# IPMC_MACP_3.net
KiCad netlist of a schematic drawn in Altium Designer
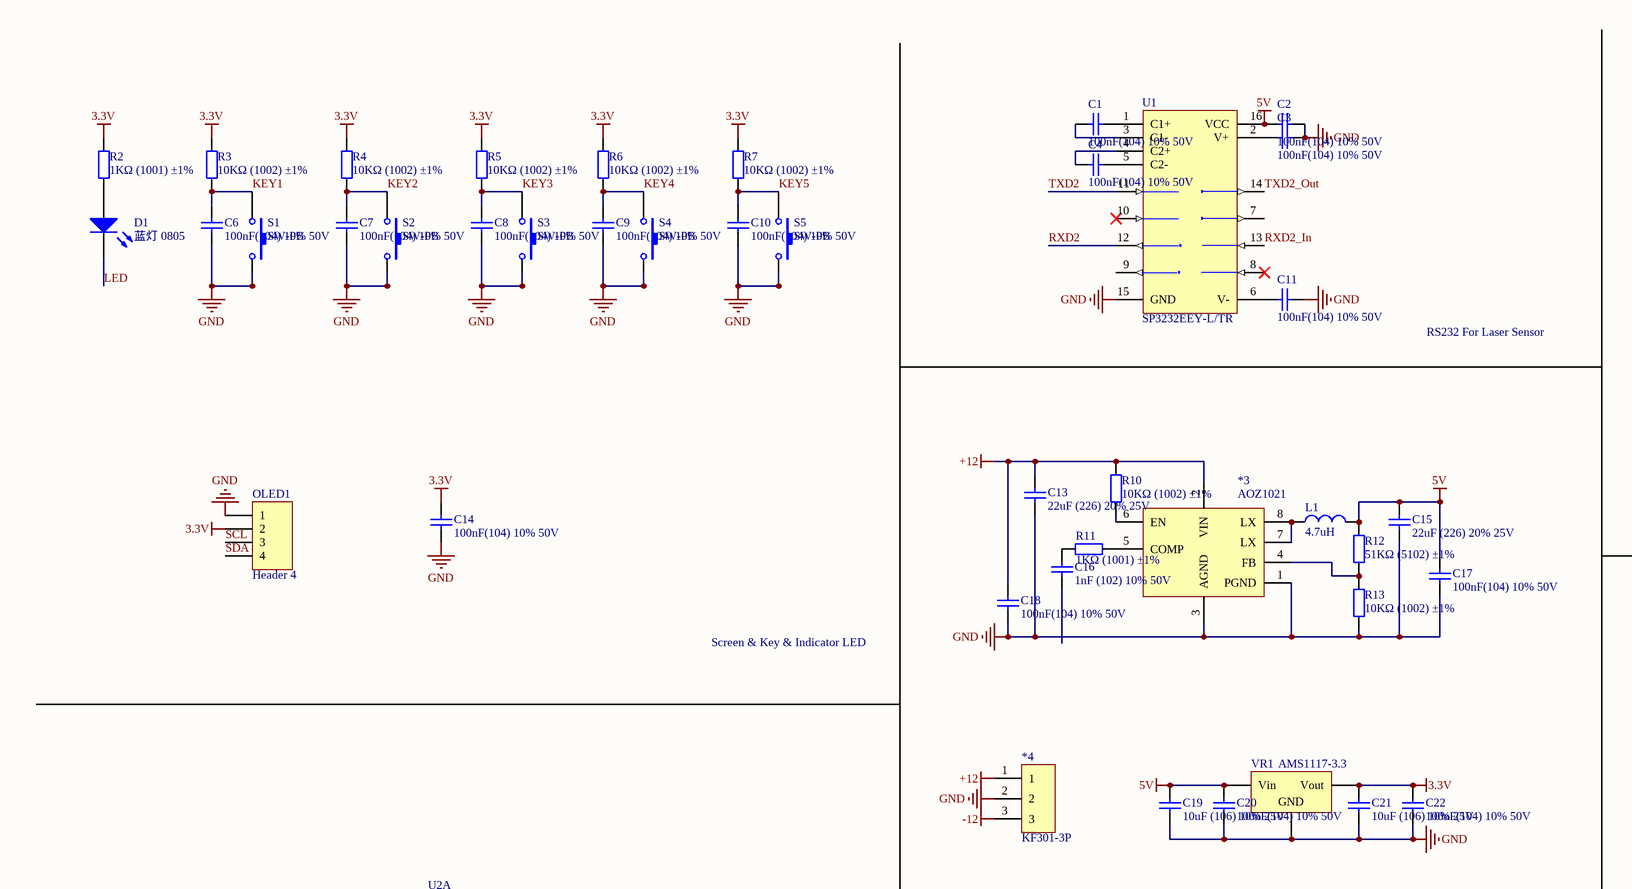
[diagram p0: IPMC_MACP 3.SchDoc, top left]
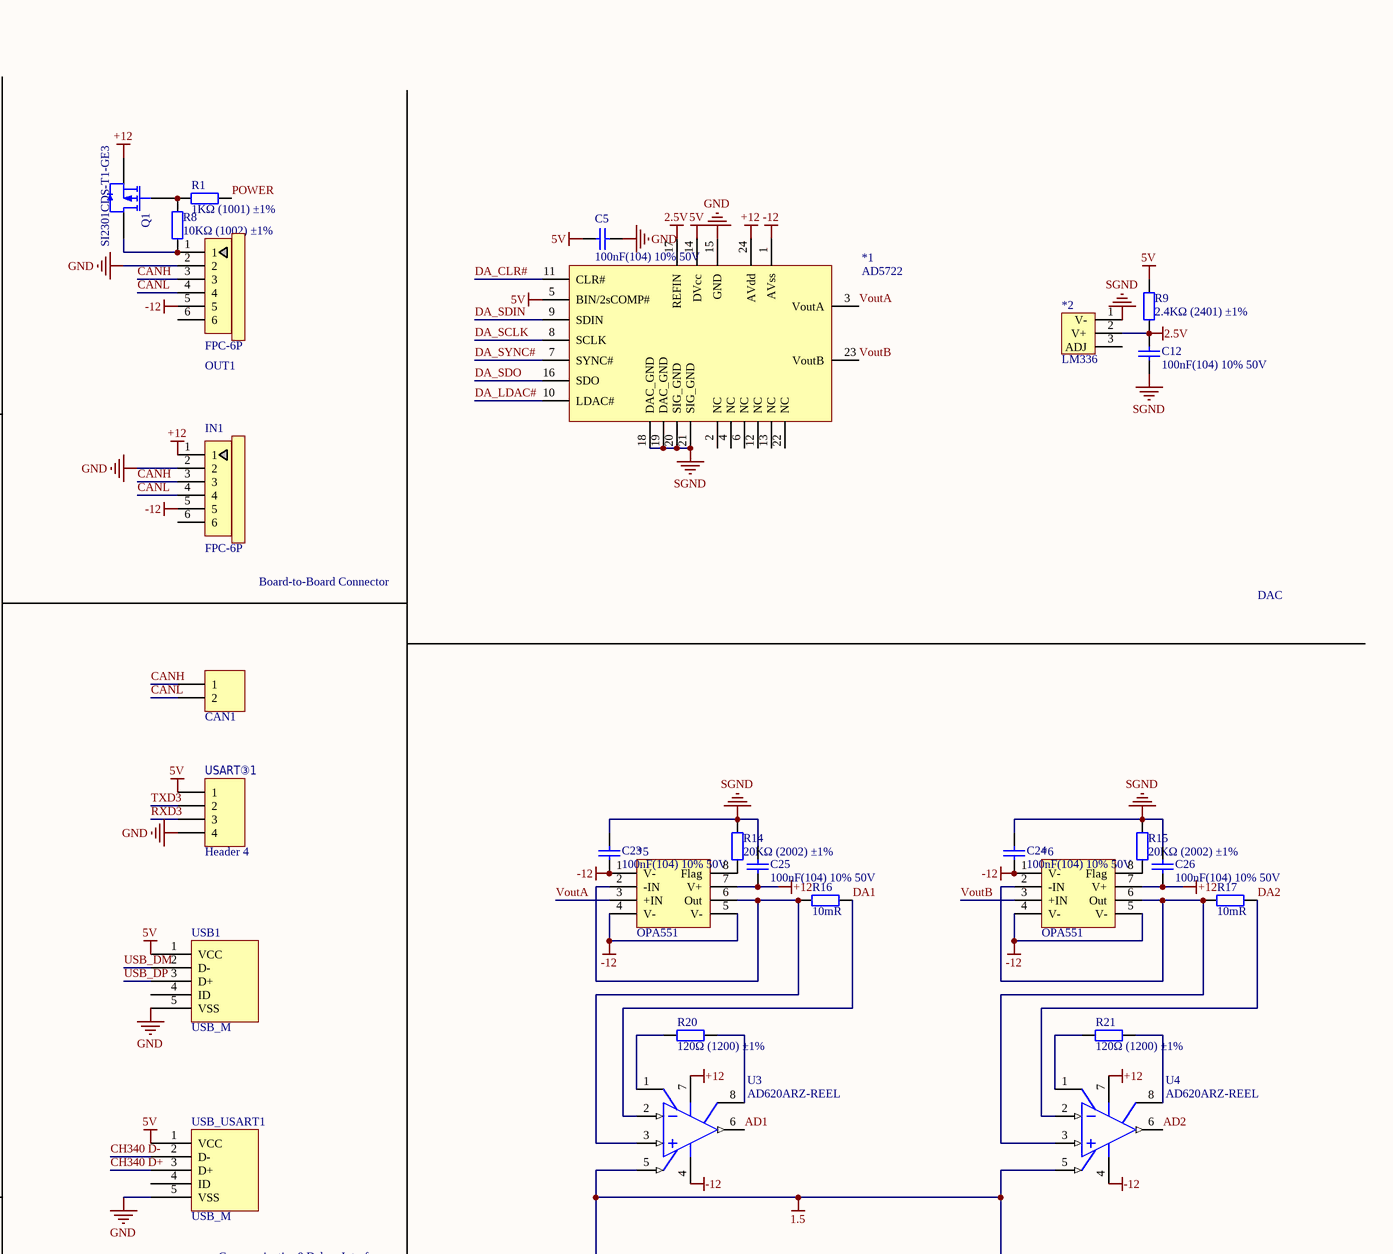
[diagram p1: IPMC_MACP 3.SchDoc, top right]
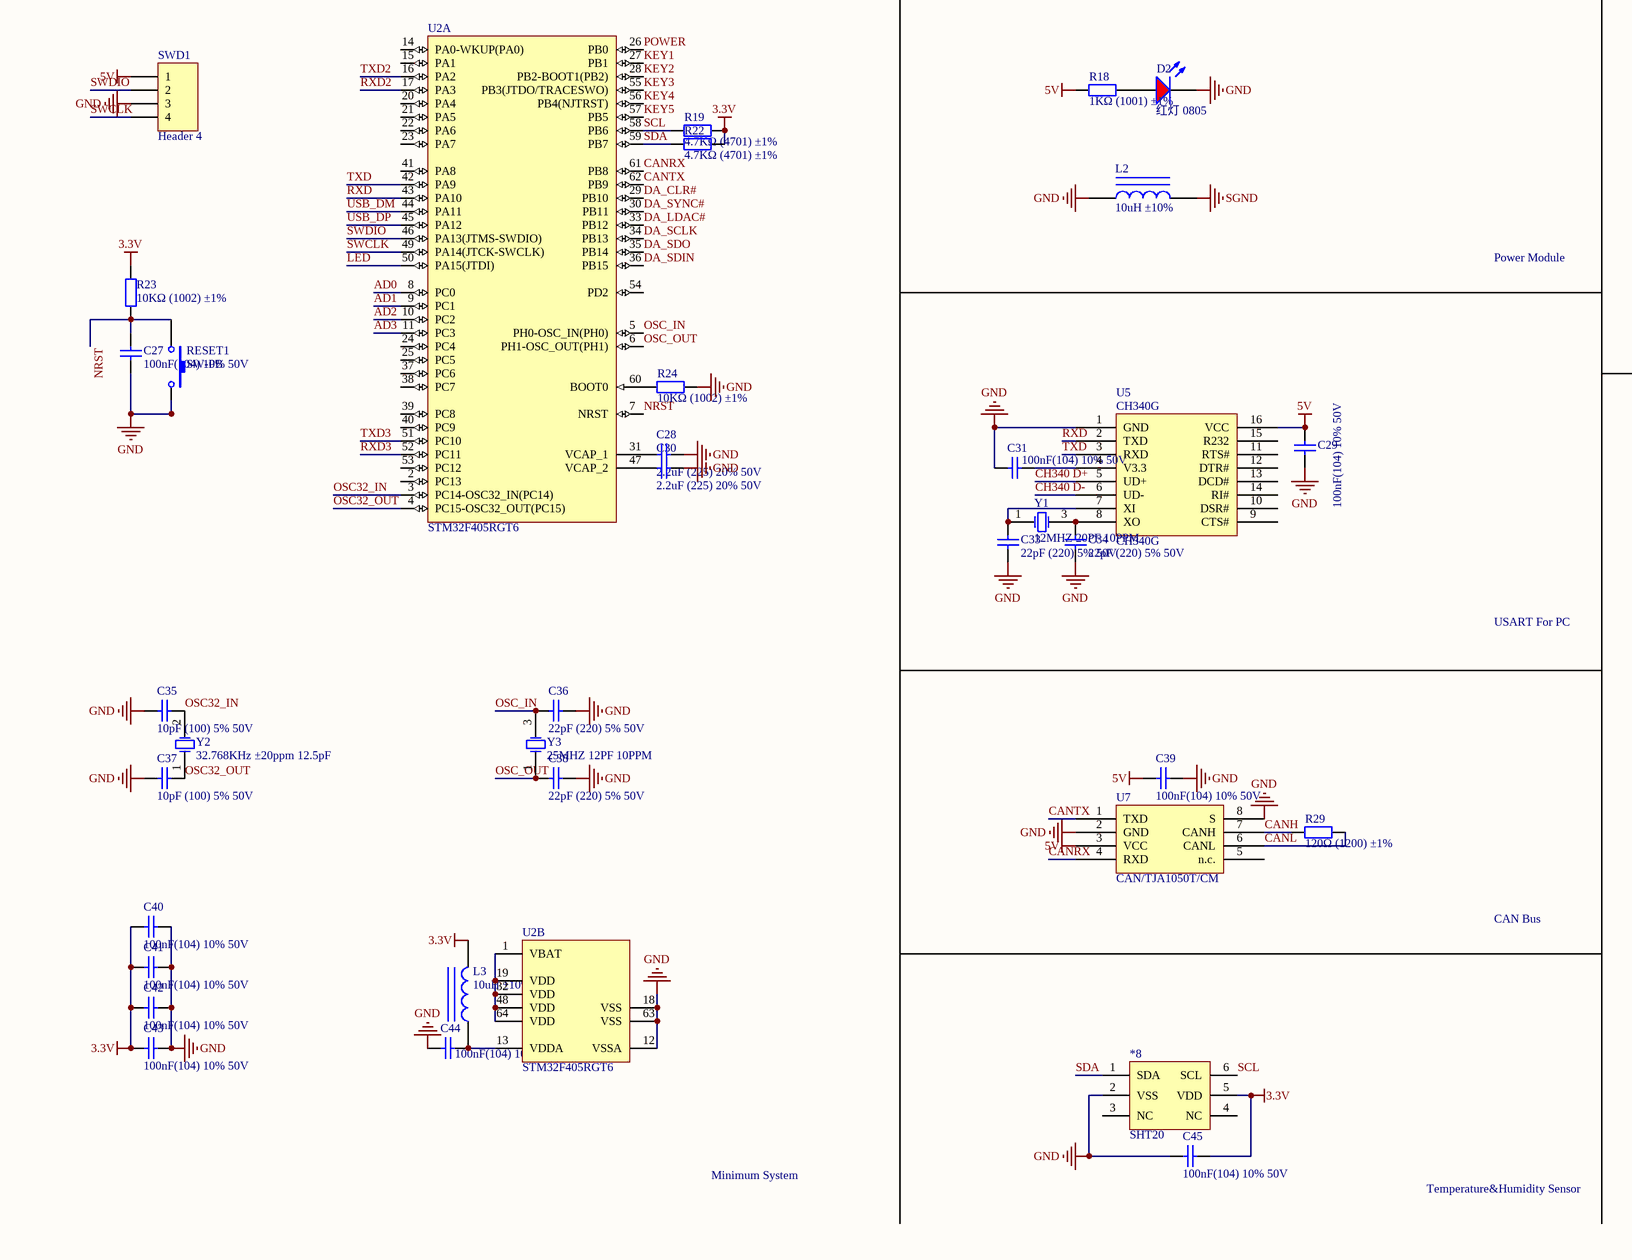
[diagram p2: IPMC_MACP 3.SchDoc, bottom left]
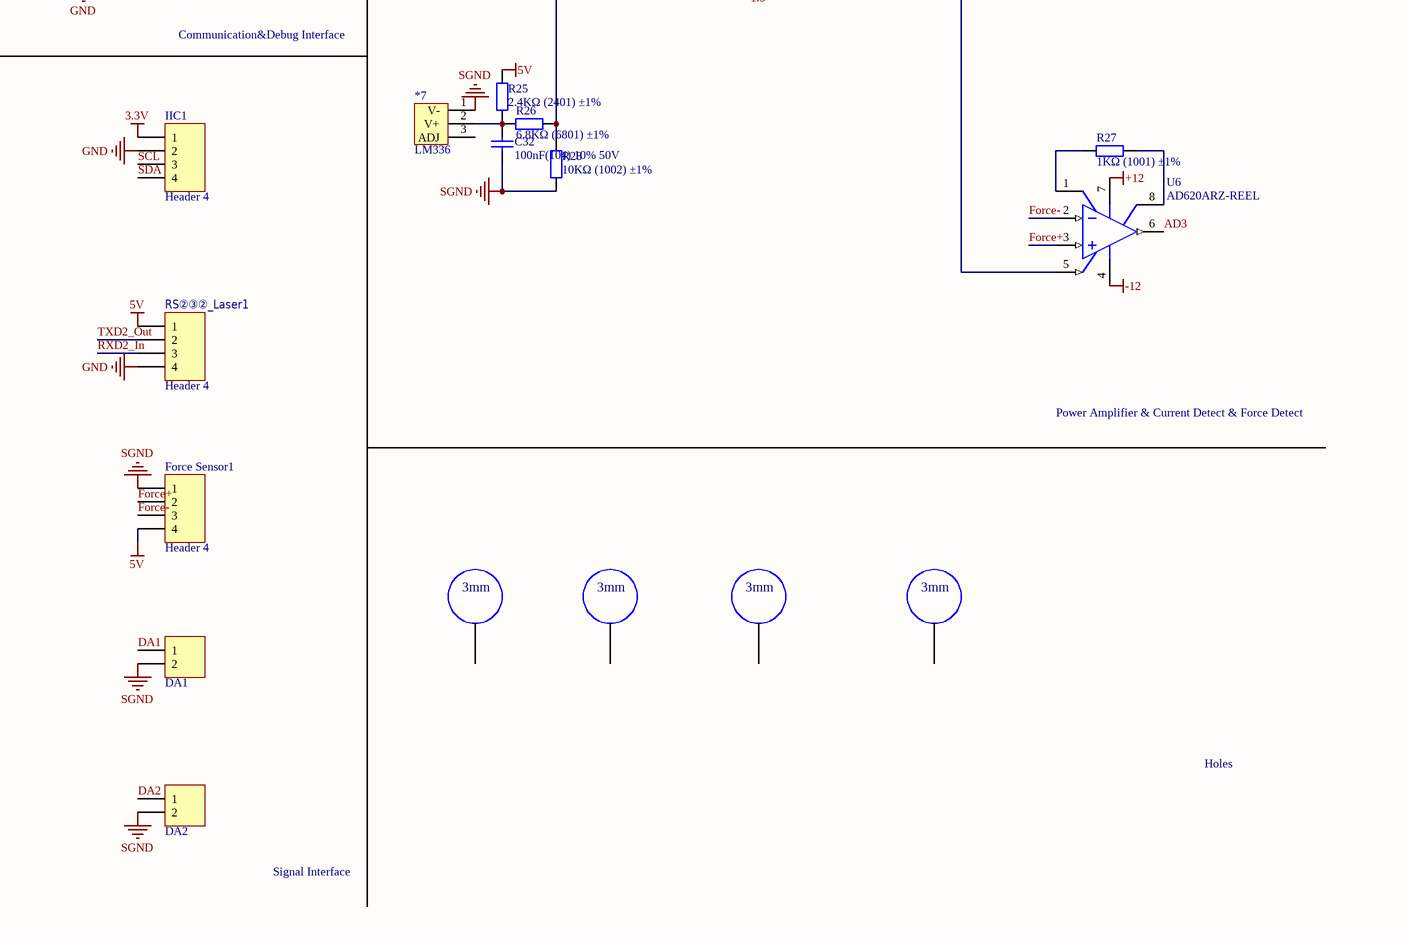
[diagram p3: IPMC_MACP 3.SchDoc, bottom right]

(export (version "E")
  (design (tool "Eeschema 10.0.6"))
  (components
    (comp (ref "*1")
      (value "AD5722")
      (footprint "TSSOP24P")
      (description "双极性DAC")
      (libsource (lib "fszhang") (part "AD5722"))
    )
    (comp (ref "*2")
      (value "LM336")
      (footprint "TO-92A")
      (description "基准电压芯片2.5/5V")
      (libsource (lib "fszhang") (part "LM336"))
    )
    (comp (ref "*3")
      (value "AOZ1021")
      (footprint "SOP-8")
      (description "3A开关电源芯片")
      (libsource (lib "fszhang") (part "AOZ1021"))
    )
    (comp (ref "*4")
      (value "KF301-3P")
      (footprint "KF301-3P")
      (description "蓝色端子")
      (libsource (lib "fszhang") (part "KF301-3P"))
    )
    (comp (ref "*5")
      (value "OPA551")
      (footprint "SOIC8_N")
      (description "高电压大电流运算放大器")
      (libsource (lib "fszhang") (part "OPA551"))
    )
    (comp (ref "*6")
      (value "OPA551")
      (footprint "SOIC8_N")
      (description "高电压大电流运算放大器")
      (libsource (lib "fszhang") (part "OPA551"))
    )
    (comp (ref "*7")
      (value "LM336")
      (footprint "TO-92A")
      (description "基准电压芯片2.5/5V")
      (libsource (lib "fszhang") (part "LM336"))
    )
    (comp (ref "*8") (value "SHT20") (footprint "DFN6") (libsource (lib "fszhang") (part "SHT20")))
    (comp (ref "C1")
      (value "100nF(104) 10% 50V")
      (footprint "0805_C")
      (description "贴片电容")
      (libsource (lib "Miscellaneous Devices LC") (part "0805 100nF(104) 10% 50V"))
    )
    (comp (ref "C2")
      (value "100nF(104) 10% 50V")
      (footprint "0805_C")
      (description "贴片电容")
      (libsource (lib "Miscellaneous Devices LC") (part "0805 100nF(104) 10% 50V"))
    )
    (comp (ref "C3")
      (value "100nF(104) 10% 50V")
      (footprint "0805_C")
      (description "贴片电容")
      (libsource (lib "Miscellaneous Devices LC") (part "0805 100nF(104) 10% 50V"))
    )
    (comp (ref "C4")
      (value "100nF(104) 10% 50V")
      (footprint "0805_C")
      (description "贴片电容")
      (libsource (lib "Miscellaneous Devices LC") (part "0805 100nF(104) 10% 50V"))
    )
    (comp (ref "C5")
      (value "100nF(104) 10% 50V")
      (footprint "0805_C")
      (description "贴片电容")
      (libsource (lib "Miscellaneous Devices LC") (part "0805 100nF(104) 10% 50V"))
    )
    (comp (ref "C6")
      (value "100nF(104) 10% 50V")
      (footprint "0805_C")
      (description "贴片电容")
      (libsource (lib "Miscellaneous Devices LC") (part "0805 100nF(104) 10% 50V"))
    )
    (comp (ref "C7")
      (value "100nF(104) 10% 50V")
      (footprint "0805_C")
      (description "贴片电容")
      (libsource (lib "Miscellaneous Devices LC") (part "0805 100nF(104) 10% 50V"))
    )
    (comp (ref "C8")
      (value "100nF(104) 10% 50V")
      (footprint "0805_C")
      (description "贴片电容")
      (libsource (lib "Miscellaneous Devices LC") (part "0805 100nF(104) 10% 50V"))
    )
    (comp (ref "C9")
      (value "100nF(104) 10% 50V")
      (footprint "0805_C")
      (description "贴片电容")
      (libsource (lib "Miscellaneous Devices LC") (part "0805 100nF(104) 10% 50V"))
    )
    (comp (ref "C10")
      (value "100nF(104) 10% 50V")
      (footprint "0805_C")
      (description "贴片电容")
      (libsource (lib "Miscellaneous Devices LC") (part "0805 100nF(104) 10% 50V"))
    )
    (comp (ref "C11")
      (value "100nF(104) 10% 50V")
      (footprint "0805_C")
      (description "贴片电容")
      (libsource (lib "Miscellaneous Devices LC") (part "0805 100nF(104) 10% 50V"))
    )
    (comp (ref "C12")
      (value "100nF(104) 10% 50V")
      (footprint "0805_C")
      (description "贴片电容")
      (libsource (lib "Miscellaneous Devices LC") (part "0805 100nF(104) 10% 50V"))
    )
    (comp (ref "C13")
      (value "22uF (226) 20% 25V")
      (footprint "0805_C")
      (description "贴片电容")
      (libsource (lib "Miscellaneous Devices LC") (part "0805 22uF (226) 20% 25V"))
    )
    (comp (ref "C14")
      (value "100nF(104) 10% 50V")
      (footprint "0805_C")
      (description "贴片电容")
      (libsource (lib "Miscellaneous Devices LC") (part "0805 100nF(104) 10% 50V"))
    )
    (comp (ref "C15")
      (value "22uF (226) 20% 25V")
      (footprint "0805_C")
      (description "贴片电容")
      (libsource (lib "Miscellaneous Devices LC") (part "0805 22uF (226) 20% 25V"))
    )
    (comp (ref "C16")
      (value "1nF (102) 10% 50V")
      (footprint "0805_C")
      (description "贴片电容")
      (libsource (lib "Miscellaneous Devices LC") (part "0805 1nF (102) 10% 50V"))
    )
    (comp (ref "C17")
      (value "100nF(104) 10% 50V")
      (footprint "0805_C")
      (description "贴片电容")
      (libsource (lib "Miscellaneous Devices LC") (part "0805 100nF(104) 10% 50V"))
    )
    (comp (ref "C18")
      (value "100nF(104) 10% 50V")
      (footprint "0805_C")
      (description "贴片电容")
      (libsource (lib "Miscellaneous Devices LC") (part "0805 100nF(104) 10% 50V"))
    )
    (comp (ref "C19")
      (value "10uF (106) 10% 25V")
      (footprint "0805_C")
      (description "贴片电容")
      (libsource (lib "Miscellaneous Devices LC") (part "0805 10uF (106) 10% 25V"))
    )
    (comp (ref "C20")
      (value "100nF(104) 10% 50V")
      (footprint "0805_C")
      (description "贴片电容")
      (libsource (lib "Miscellaneous Devices LC") (part "0805 100nF(104) 10% 50V"))
    )
    (comp (ref "C21")
      (value "10uF (106) 10% 25V")
      (footprint "0805_C")
      (description "贴片电容")
      (libsource (lib "Miscellaneous Devices LC") (part "0805 10uF (106) 10% 25V"))
    )
    (comp (ref "C22")
      (value "100nF(104) 10% 50V")
      (footprint "0805_C")
      (description "贴片电容")
      (libsource (lib "Miscellaneous Devices LC") (part "0805 100nF(104) 10% 50V"))
    )
    (comp (ref "C23")
      (value "100nF(104) 10% 50V")
      (footprint "0805_C")
      (description "贴片电容")
      (libsource (lib "Miscellaneous Devices LC") (part "0805 100nF(104) 10% 50V"))
    )
    (comp (ref "C24")
      (value "100nF(104) 10% 50V")
      (footprint "0805_C")
      (description "贴片电容")
      (libsource (lib "Miscellaneous Devices LC") (part "0805 100nF(104) 10% 50V"))
    )
    (comp (ref "C25")
      (value "100nF(104) 10% 50V")
      (footprint "0805_C")
      (description "贴片电容")
      (libsource (lib "Miscellaneous Devices LC") (part "0805 100nF(104) 10% 50V"))
    )
    (comp (ref "C26")
      (value "100nF(104) 10% 50V")
      (footprint "0805_C")
      (description "贴片电容")
      (libsource (lib "Miscellaneous Devices LC") (part "0805 100nF(104) 10% 50V"))
    )
    (comp (ref "C27")
      (value "100nF(104) 10% 50V")
      (footprint "0805_C")
      (description "贴片电容")
      (libsource (lib "Miscellaneous Devices LC") (part "0805 100nF(104) 10% 50V"))
    )
    (comp (ref "C28")
      (value "2.2uF (225) 20% 50V")
      (footprint "0805_C")
      (description "贴片电容")
      (libsource (lib "Miscellaneous Devices LC") (part "0805 2.2uF (225) 20% 50V"))
    )
    (comp (ref "C29")
      (value "100nF(104) 10% 50V")
      (footprint "0805_C")
      (description "贴片电容")
      (libsource (lib "Miscellaneous Devices LC") (part "0805 100nF(104) 10% 50V"))
    )
    (comp (ref "C30")
      (value "2.2uF (225) 20% 50V")
      (footprint "0805_C")
      (description "贴片电容")
      (libsource (lib "Miscellaneous Devices LC") (part "0805 2.2uF (225) 20% 50V"))
    )
    (comp (ref "C31")
      (value "100nF(104) 10% 50V")
      (footprint "0805_C")
      (description "贴片电容")
      (libsource (lib "Miscellaneous Devices LC") (part "0805 100nF(104) 10% 50V"))
    )
    (comp (ref "C32")
      (value "100nF(104) 10% 50V")
      (footprint "0805_C")
      (description "贴片电容")
      (libsource (lib "Miscellaneous Devices LC") (part "0805 100nF(104) 10% 50V"))
    )
    (comp (ref "C33")
      (value "22pF (220) 5% 50V")
      (footprint "0805_C")
      (description "贴片电容")
      (libsource (lib "Miscellaneous Devices LC") (part "0805 22pF (220) 5% 50V"))
    )
    (comp (ref "C34")
      (value "22pF (220) 5% 50V")
      (footprint "0805_C")
      (description "贴片电容")
      (libsource (lib "Miscellaneous Devices LC") (part "0805 22pF (220) 5% 50V"))
    )
    (comp (ref "C35")
      (value "10pF (100) 5% 50V")
      (footprint "0805_C")
      (description "贴片电容")
      (libsource (lib "Miscellaneous Devices LC") (part "0805 10pF (100) 5% 50V"))
    )
    (comp (ref "C36")
      (value "22pF (220) 5% 50V")
      (footprint "0805_C")
      (description "贴片电容")
      (libsource (lib "Miscellaneous Devices LC") (part "0805 22pF (220) 5% 50V"))
    )
    (comp (ref "C37")
      (value "10pF (100) 5% 50V")
      (footprint "0805_C")
      (description "贴片电容")
      (libsource (lib "Miscellaneous Devices LC") (part "0805 10pF (100) 5% 50V"))
    )
    (comp (ref "C38")
      (value "22pF (220) 5% 50V")
      (footprint "0805_C")
      (description "贴片电容")
      (libsource (lib "Miscellaneous Devices LC") (part "0805 22pF (220) 5% 50V"))
    )
    (comp (ref "C39")
      (value "100nF(104) 10% 50V")
      (footprint "0805_C")
      (description "贴片电容")
      (libsource (lib "Miscellaneous Devices LC") (part "0805 100nF(104) 10% 50V"))
    )
    (comp (ref "C40")
      (value "100nF(104) 10% 50V")
      (footprint "0805_C")
      (description "贴片电容")
      (libsource (lib "Miscellaneous Devices LC") (part "0805 100nF(104) 10% 50V"))
    )
    (comp (ref "C41")
      (value "100nF(104) 10% 50V")
      (footprint "0805_C")
      (description "贴片电容")
      (libsource (lib "Miscellaneous Devices LC") (part "0805 100nF(104) 10% 50V"))
    )
    (comp (ref "C42")
      (value "100nF(104) 10% 50V")
      (footprint "0805_C")
      (description "贴片电容")
      (libsource (lib "Miscellaneous Devices LC") (part "0805 100nF(104) 10% 50V"))
    )
    (comp (ref "C43")
      (value "100nF(104) 10% 50V")
      (footprint "0805_C")
      (description "贴片电容")
      (libsource (lib "Miscellaneous Devices LC") (part "0805 100nF(104) 10% 50V"))
    )
    (comp (ref "C44")
      (value "100nF(104) 10% 50V")
      (footprint "0805_C")
      (description "贴片电容")
      (libsource (lib "Miscellaneous Devices LC") (part "0805 100nF(104) 10% 50V"))
    )
    (comp (ref "C45")
      (value "100nF(104) 10% 50V")
      (footprint "0805_C")
      (description "贴片电容")
      (libsource (lib "Miscellaneous Devices LC") (part "0805 100nF(104) 10% 50V"))
    )
    (comp (ref "CAN1")
      (value "Header 2")
      (footprint "HDR2X1_A")
      (description "接插件")
      (fields (field (name "PUBLISHER") "Altium Limited"))
      (libsource (lib "fszhang") (part "Header 2"))
    )
    (comp (ref "D1")
      (value "蓝灯 0805")
      (footprint "0805_LED_S1")
      (description "发光二极管")
      (libsource (lib "Miscellaneous Devices LC") (part "0805 蓝灯"))
    )
    (comp (ref "D2")
      (value "红灯 0805")
      (footprint "0805_LED_S1")
      (description "发光二极管")
      (libsource (lib "Miscellaneous Devices LC") (part "0805 红灯"))
    )
    (comp (ref "DA1")
      (value "Header 2")
      (footprint "HDR2X1_A")
      (description "接插件")
      (fields (field (name "PUBLISHER") "Altium Limited"))
      (libsource (lib "fszhang") (part "Header 2"))
    )
    (comp (ref "DA2")
      (value "Header 2")
      (footprint "HDR2X1_A")
      (description "接插件")
      (fields (field (name "PUBLISHER") "Altium Limited"))
      (libsource (lib "fszhang") (part "Header 2"))
    )
    (comp (ref "Force Sensor1")
      (value "Header 4")
      (footprint "HDR1X4")
      (description "Header, 4-Pin")
      (fields (field (name "PUBLISHER") "Altium Limited"))
      (libsource (lib "Miscellaneous Connectors") (part "Header 4"))
    )
    (comp (ref "IIC1")
      (value "Header 4")
      (footprint "HDR1X4")
      (description "Header, 4-Pin")
      (fields (field (name "PUBLISHER") "Altium Limited"))
      (libsource (lib "Miscellaneous Connectors") (part "Header 4"))
    )
    (comp (ref "IN1")
      (value "FPC-6P")
      (footprint "FPC1.0-6P-A")
      (description "FPC排线连接器")
      (libsource (lib "fszhang") (part "FPC-6P"))
    )
    (comp (ref "L1")
      (value "4.7uH")
      (footprint "06030")
      (description "电感")
      (fields (field (name "PUBLISHER") "Altium Limited"))
      (libsource (lib "fszhang") (part "Inductor"))
    )
    (comp (ref "L2")
      (value "10uH ±10%")
      (footprint "0805_L")
      (description "贴片电感")
      (libsource (lib "Miscellaneous Devices LC") (part "0805 10uH 10%"))
    )
    (comp (ref "L3")
      (value "10uH ±10%")
      (footprint "0805_L")
      (description "贴片电感")
      (libsource (lib "Miscellaneous Devices LC") (part "0805 10uH 10%"))
    )
    (comp (ref "OLED1")
      (value "Header 4")
      (footprint "HDR1X4")
      (description "Header, 4-Pin")
      (fields (field (name "PUBLISHER") "Altium Limited"))
      (libsource (lib "Miscellaneous Connectors") (part "Header 4"))
    )
    (comp (ref "OUT1")
      (value "FPC-6P")
      (footprint "FPC1.0-6P-A")
      (description "FPC排线连接器")
      (libsource (lib "fszhang") (part "FPC-6P"))
    )
    (comp (ref "Q1")
      (value "SI2301CDS-T1-GE3")
      (footprint "SOT-23(SOT-23-3)")
      (description "MOS(场效应管)")
      (libsource (lib "Miscellaneous Devices LC") (part "SI2301CDS-T1-GE3"))
    )
    (comp (ref "R1")
      (value "1KΩ (1001) ±1%")
      (footprint "0805_R")
      (description "贴片电阻")
      (libsource (lib "Miscellaneous Devices LC") (part "0805 1KΩ (1001) 1%"))
    )
    (comp (ref "R2")
      (value "1KΩ (1001) ±1%")
      (footprint "0805_R")
      (description "贴片电阻")
      (libsource (lib "") (part "0805 1KΩ (1001) 1%_2"))
    )
    (comp (ref "R3")
      (value "10KΩ (1002) ±1%")
      (footprint "0805_R")
      (description "贴片电阻")
      (libsource (lib "Miscellaneous Devices LC") (part "0805 10KΩ (1002) 1%"))
    )
    (comp (ref "R4")
      (value "10KΩ (1002) ±1%")
      (footprint "0805_R")
      (description "贴片电阻")
      (libsource (lib "Miscellaneous Devices LC") (part "0805 10KΩ (1002) 1%"))
    )
    (comp (ref "R5")
      (value "10KΩ (1002) ±1%")
      (footprint "0805_R")
      (description "贴片电阻")
      (libsource (lib "Miscellaneous Devices LC") (part "0805 10KΩ (1002) 1%"))
    )
    (comp (ref "R6")
      (value "10KΩ (1002) ±1%")
      (footprint "0805_R")
      (description "贴片电阻")
      (libsource (lib "Miscellaneous Devices LC") (part "0805 10KΩ (1002) 1%"))
    )
    (comp (ref "R7")
      (value "10KΩ (1002) ±1%")
      (footprint "0805_R")
      (description "贴片电阻")
      (libsource (lib "Miscellaneous Devices LC") (part "0805 10KΩ (1002) 1%"))
    )
    (comp (ref "R8")
      (value "10KΩ (1002) ±1%")
      (footprint "0805_R")
      (description "贴片电阻")
      (libsource (lib "Miscellaneous Devices LC") (part "0805 10KΩ (1002) 1%"))
    )
    (comp (ref "R9")
      (value "2.4KΩ (2401) ±1%")
      (footprint "0805_R")
      (description "贴片电阻")
      (libsource (lib "Miscellaneous Devices LC") (part "0805 2.4KΩ (2401) 1%"))
    )
    (comp (ref "R10")
      (value "10KΩ (1002) ±1%")
      (footprint "0805_R")
      (description "贴片电阻")
      (libsource (lib "Miscellaneous Devices LC") (part "0805 10KΩ (1002) 1%"))
    )
    (comp (ref "R11")
      (value "1KΩ (1001) ±1%")
      (footprint "0805_R")
      (description "贴片电阻")
      (libsource (lib "Miscellaneous Devices LC") (part "0805 1KΩ (1001) 1%"))
    )
    (comp (ref "R12")
      (value "51KΩ (5102) ±1%")
      (footprint "0805_R")
      (description "贴片电阻")
      (libsource (lib "Miscellaneous Devices LC") (part "0805 51KΩ (5102) 1%"))
    )
    (comp (ref "R13")
      (value "10KΩ (1002) ±1%")
      (footprint "0805_R")
      (description "贴片电阻")
      (libsource (lib "") (part "0805 10KΩ (1002) 1%_1"))
    )
    (comp (ref "R14")
      (value "20KΩ (2002) ±1%")
      (footprint "0805_R")
      (description "贴片电阻")
      (libsource (lib "Miscellaneous Devices LC") (part "0805 20KΩ (2002) 1%"))
    )
    (comp (ref "R15")
      (value "20KΩ (2002) ±1%")
      (footprint "0805_R")
      (description "贴片电阻")
      (libsource (lib "Miscellaneous Devices LC") (part "0805 20KΩ (2002) 1%"))
    )
    (comp (ref "R16")
      (value "10mR")
      (footprint "2512")
      (description "贴片电阻")
      (fields (field (name "PUBLISHER") "Altium Limited"))
      (libsource (lib "fszhang") (part "Res1"))
    )
    (comp (ref "R17")
      (value "10mR")
      (footprint "2512")
      (description "贴片电阻")
      (fields (field (name "PUBLISHER") "Altium Limited"))
      (libsource (lib "fszhang") (part "Res1"))
    )
    (comp (ref "R18")
      (value "1KΩ (1001) ±1%")
      (footprint "0805_R")
      (description "贴片电阻")
      (libsource (lib "") (part "0805 1KΩ (1001) 1%_1"))
    )
    (comp (ref "R19")
      (value "4.7KΩ (4701) ±1%")
      (footprint "0805_R")
      (description "贴片电阻")
      (libsource (lib "Miscellaneous Devices LC") (part "0805 4.7KΩ (4701) 1%"))
    )
    (comp (ref "R20")
      (value "120Ω (1200) ±1%")
      (footprint "0805_R")
      (description "贴片电阻")
      (libsource (lib "Miscellaneous Devices LC") (part "0805 120Ω (1200) 1%"))
    )
    (comp (ref "R21")
      (value "120Ω (1200) ±1%")
      (footprint "0805_R")
      (description "贴片电阻")
      (libsource (lib "Miscellaneous Devices LC") (part "0805 120Ω (1200) 1%"))
    )
    (comp (ref "R22")
      (value "4.7KΩ (4701) ±1%")
      (footprint "0805_R")
      (description "贴片电阻")
      (libsource (lib "Miscellaneous Devices LC") (part "0805 4.7KΩ (4701) 1%"))
    )
    (comp (ref "R23")
      (value "10KΩ (1002) ±1%")
      (footprint "0805_R")
      (description "贴片电阻")
      (libsource (lib "Miscellaneous Devices LC") (part "0805 10KΩ (1002) 1%"))
    )
    (comp (ref "R24")
      (value "10KΩ (1002) ±1%")
      (footprint "0805_R")
      (description "贴片电阻")
      (libsource (lib "") (part "0805 10KΩ (1002) 1%_2"))
    )
    (comp (ref "R25")
      (value "2.4KΩ (2401) ±1%")
      (footprint "0805_R")
      (description "贴片电阻")
      (libsource (lib "Miscellaneous Devices LC") (part "0805 2.4KΩ (2401) 1%"))
    )
    (comp (ref "R26")
      (value "6.8KΩ (6801) ±1%")
      (footprint "0805_R")
      (description "贴片电阻")
      (libsource (lib "Miscellaneous Devices LC") (part "0805 6.8KΩ (6801) 1%"))
    )
    (comp (ref "R27")
      (value "1KΩ (1001) ±1%")
      (footprint "0805_R")
      (description "贴片电阻")
      (libsource (lib "") (part "0805 1KΩ (1001) 1%_1"))
    )
    (comp (ref "R28")
      (value "10KΩ (1002) ±1%")
      (footprint "0805_R")
      (description "贴片电阻")
      (libsource (lib "Miscellaneous Devices LC") (part "0805 10KΩ (1002) 1%"))
    )
    (comp (ref "R29")
      (value "120Ω (1200) ±1%")
      (footprint "0805_R")
      (description "贴片电阻")
      (libsource (lib "Miscellaneous Devices LC") (part "0805 120Ω (1200) 1%"))
    )
    (comp (ref "RESET1")
      (value "SW-PB")
      (footprint "SW_PB2_A1")
      (description "微动开关")
      (fields (field (name "PUBLISHER") "Altium Limited"))
      (libsource (lib "fszhang") (part "SW-PB"))
    )
    (comp (ref "RS②③②_Laser1")
      (value "Header 4")
      (footprint "HDR1X4")
      (description "Header, 4-Pin")
      (fields (field (name "PUBLISHER") "Altium Limited"))
      (libsource (lib "Miscellaneous Connectors") (part "Header 4"))
    )
    (comp (ref "S1")
      (value "SW-PB")
      (footprint "SW_PB2_A1")
      (description "微动开关")
      (fields (field (name "PUBLISHER") "Altium Limited"))
      (libsource (lib "fszhang") (part "SW-PB"))
    )
    (comp (ref "S2")
      (value "SW-PB")
      (footprint "SW_PB2_A1")
      (description "微动开关")
      (fields (field (name "PUBLISHER") "Altium Limited"))
      (libsource (lib "fszhang") (part "SW-PB"))
    )
    (comp (ref "S3")
      (value "SW-PB")
      (footprint "SW_PB2_A1")
      (description "微动开关")
      (fields (field (name "PUBLISHER") "Altium Limited"))
      (libsource (lib "fszhang") (part "SW-PB"))
    )
    (comp (ref "S4")
      (value "SW-PB")
      (footprint "SW_PB2_A1")
      (description "微动开关")
      (fields (field (name "PUBLISHER") "Altium Limited"))
      (libsource (lib "fszhang") (part "SW-PB"))
    )
    (comp (ref "S5")
      (value "SW-PB")
      (footprint "SW_PB2_A1")
      (description "微动开关")
      (fields (field (name "PUBLISHER") "Altium Limited"))
      (libsource (lib "fszhang") (part "SW-PB"))
    )
    (comp (ref "SWD1")
      (value "Header 4")
      (footprint "HDR1X4")
      (description "Header, 4-Pin")
      (fields (field (name "PUBLISHER") "Altium Limited"))
      (libsource (lib "Miscellaneous Connectors") (part "Header 4"))
    )
    (comp (ref "T1") (value "M3铜柱螺丝孔") (footprint "螺丝孔-3mm") (libsource (lib "fszhang") (part "M3铜柱螺丝孔")))
    (comp (ref "T2") (value "M3铜柱螺丝孔") (footprint "螺丝孔-3mm") (libsource (lib "fszhang") (part "M3铜柱螺丝孔")))
    (comp (ref "T3") (value "M3铜柱螺丝孔") (footprint "螺丝孔-3mm") (libsource (lib "fszhang") (part "M3铜柱螺丝孔")))
    (comp (ref "T4") (value "M3铜柱螺丝孔") (footprint "螺丝孔-3mm") (libsource (lib "fszhang") (part "M3铜柱螺丝孔")))
    (comp (ref "U1")
      (value "SP3232EEY-L/TR")
      (footprint "TSSOP-16")
      (description "RS232")
      (libsource (lib "Miscellaneous Devices LC") (part "SP3232EEY-L/TR"))
    )
    (comp (ref "U2")
      (value "STM32F405RGT6")
      (footprint "STM-LQFP64_L")
      (fields (field (name "MANUFACTURER") "STMicroelectronics"))
      (libsource (lib "STMicroelectronics STM32 F4") (part "STM32F405RGT6"))
    )
    (comp (ref "U3")
      (value "AD620ARZ-REEL")
      (footprint "SOIC-8_150mil")
      (description "仪放")
      (libsource (lib "Miscellaneous Devices LC") (part "AD620ARZ-REEL"))
    )
    (comp (ref "U4")
      (value "AD620ARZ-REEL")
      (footprint "SOIC-8_150mil")
      (description "仪放")
      (libsource (lib "Miscellaneous Devices LC") (part "AD620ARZ-REEL"))
    )
    (comp (ref "U5")
      (value "CH340G")
      (footprint "SOIC-16_150mil")
      (description "USB")
      (libsource (lib "Miscellaneous Devices LC") (part "CH340G"))
    )
    (comp (ref "U6")
      (value "AD620ARZ-REEL")
      (footprint "SOIC-8_150mil")
      (description "仪放")
      (libsource (lib "Miscellaneous Devices LC") (part "AD620ARZ-REEL"))
    )
    (comp (ref "U7")
      (value "CAN/TJA1050T/CM")
      (footprint "SOIC-8_150mil")
      (description "CAN")
      (libsource (lib "Miscellaneous Devices LC") (part "CAN/TJA1050T/CM"))
    )
    (comp (ref "USART③1")
      (value "Header 4")
      (footprint "HDR1X4")
      (description "Header, 4-Pin")
      (fields (field (name "PUBLISHER") "Altium Limited"))
      (libsource (lib "Miscellaneous Connectors") (part "Header 4"))
    )
    (comp (ref "USB1")
      (value "USB_M")
      (footprint "USB_MICRO")
      (description "MicroUSB接口")
      (libsource (lib "fszhang") (part "USB_M"))
    )
    (comp (ref "USB_USART1")
      (value "USB_M")
      (footprint "USB_MICRO")
      (description "MicroUSB接口")
      (libsource (lib "fszhang") (part "USB_M"))
    )
    (comp (ref "VR1")
      (value "AMS1117-3.3")
      (footprint "SOT-223")
      (description "低压差线性稳压(LDO)")
      (libsource (lib "Miscellaneous Devices LC") (part "SOT-223 AMS1117-3.3"))
    )
    (comp (ref "Y1")
      (value "12MHZ 20PF 10PPM")
      (footprint "SMD-3225_4P")
      (description "贴片晶振")
      (libsource (lib "Miscellaneous Devices LC") (part "SMD-3225_4P  12MHZ 20PF 10PPM"))
    )
    (comp (ref "Y2")
      (value "32.768KHz ±20ppm 12.5pF")
      (footprint "SMD-3215_2P FC - 135")
      (description "贴片晶振")
      (libsource (lib "Miscellaneous Devices LC") (part "SMD-3215_2P 32.768KHz 20ppm 12.5pF"))
    )
    (comp (ref "Y3")
      (value "25MHZ 12PF 10PPM")
      (footprint "SMD-3225_4P")
      (description "贴片晶振")
      (libsource (lib "Miscellaneous Devices LC") (part "SMD-3225_4P  25MHZ 12PF 10PPM"))
    )
  )
  (nets
    (net (code "1") (name "+12") (class "Default")
      (node (ref "*1") (pin "24") (pinfunction "AVdd_24") (pintype "passive"))
      (node (ref "*3") (pin "2") (pinfunction "VIN_2") (pintype "passive"))
      (node (ref "*4") (pin "1") (pinfunction "1_1") (pintype "passive"))
      (node (ref "*5") (pin "7") (pinfunction "V+_7") (pintype "passive"))
      (node (ref "*6") (pin "7") (pinfunction "V+_7") (pintype "passive"))
      (node (ref "C13") (pin "2") (pinfunction "2_2") (pintype "passive"))
      (node (ref "C18") (pin "1") (pinfunction "1_1") (pintype "passive"))
      (node (ref "C25") (pin "1") (pinfunction "1_1") (pintype "passive"))
      (node (ref "C26") (pin "1") (pinfunction "1_1") (pintype "passive"))
      (node (ref "IN1") (pin "1") (pinfunction "1_1") (pintype "passive"))
      (node (ref "Q1") (pin "2") (pinfunction "S_2") (pintype "passive"))
      (node (ref "R10") (pin "1") (pinfunction "1_1") (pintype "passive"))
      (node (ref "U3") (pin "7") (pinfunction "V+_7") (pintype "power_in"))
      (node (ref "U4") (pin "7") (pinfunction "V+_7") (pintype "power_in"))
      (node (ref "U6") (pin "7") (pinfunction "V+_7") (pintype "power_in"))
    )
    (net (code "2") (name "-12") (class "Default")
      (node (ref "*1") (pin "1") (pinfunction "AVss_1") (pintype "passive"))
      (node (ref "*4") (pin "3") (pinfunction "3_3") (pintype "passive"))
      (node (ref "*5") (pin "1") (pinfunction "V-_1") (pintype "passive"))
      (node (ref "*5") (pin "4") (pinfunction "V-_4") (pintype "passive"))
      (node (ref "*5") (pin "5") (pinfunction "V-_5") (pintype "passive"))
      (node (ref "*6") (pin "1") (pinfunction "V-_1") (pintype "passive"))
      (node (ref "*6") (pin "4") (pinfunction "V-_4") (pintype "passive"))
      (node (ref "*6") (pin "5") (pinfunction "V-_5") (pintype "passive"))
      (node (ref "C23") (pin "1") (pinfunction "1_1") (pintype "passive"))
      (node (ref "C24") (pin "1") (pinfunction "1_1") (pintype "passive"))
      (node (ref "IN1") (pin "5") (pinfunction "5_5") (pintype "passive"))
      (node (ref "OUT1") (pin "5") (pinfunction "5_5") (pintype "passive"))
      (node (ref "U3") (pin "4") (pinfunction "V-_4") (pintype "power_in"))
      (node (ref "U4") (pin "4") (pinfunction "V-_4") (pintype "power_in"))
      (node (ref "U6") (pin "4") (pinfunction "V-_4") (pintype "power_in"))
    )
    (net (code "3") (name "/AD0") (class "Default")
      (node (ref "U2") (pin "8") (pinfunction "PC0_8") (pintype "bidirectional"))
    )
    (net (code "4") (name "/AD1") (class "Default")
      (node (ref "U2") (pin "9") (pinfunction "PC1_9") (pintype "bidirectional"))
      (node (ref "U3") (pin "6") (pinfunction "OUT_6") (pintype "output"))
    )
    (net (code "5") (name "/AD2") (class "Default")
      (node (ref "U2") (pin "10") (pinfunction "PC2_10") (pintype "bidirectional"))
      (node (ref "U4") (pin "6") (pinfunction "OUT_6") (pintype "output"))
    )
    (net (code "6") (name "/AD3") (class "Default")
      (node (ref "U2") (pin "11") (pinfunction "PC3_11") (pintype "bidirectional"))
      (node (ref "U6") (pin "6") (pinfunction "OUT_6") (pintype "output"))
    )
    (net (code "7") (name "/CANH") (class "Default")
      (node (ref "CAN1") (pin "1") (pinfunction "1_1") (pintype "passive"))
      (node (ref "IN1") (pin "3") (pinfunction "3_3") (pintype "passive"))
      (node (ref "OUT1") (pin "3") (pinfunction "3_3") (pintype "passive"))
      (node (ref "R29") (pin "1") (pinfunction "1_1") (pintype "passive"))
      (node (ref "U7") (pin "7") (pinfunction "CANH_7") (pintype "passive"))
    )
    (net (code "8") (name "/CANL") (class "Default")
      (node (ref "CAN1") (pin "2") (pinfunction "2_2") (pintype "passive"))
      (node (ref "IN1") (pin "4") (pinfunction "4_4") (pintype "passive"))
      (node (ref "OUT1") (pin "4") (pinfunction "4_4") (pintype "passive"))
      (node (ref "R29") (pin "2") (pinfunction "2_2") (pintype "passive"))
      (node (ref "U7") (pin "6") (pinfunction "CANL_6") (pintype "passive"))
    )
    (net (code "9") (name "/CANRX") (class "Default")
      (node (ref "U2") (pin "61") (pinfunction "PB8_61") (pintype "bidirectional"))
      (node (ref "U7") (pin "4") (pinfunction "RXD_4") (pintype "passive"))
    )
    (net (code "10") (name "/CANTX") (class "Default")
      (node (ref "U2") (pin "62") (pinfunction "PB9_62") (pintype "bidirectional"))
      (node (ref "U7") (pin "1") (pinfunction "TXD_1") (pintype "passive"))
    )
    (net (code "11") (name "/CH340 D+") (class "Default")
      (node (ref "U5") (pin "5") (pinfunction "UD+_5") (pintype "passive"))
      (node (ref "USB_USART1") (pin "3") (pinfunction "D+_3") (pintype "passive"))
    )
    (net (code "12") (name "/CH340 D-") (class "Default")
      (node (ref "U5") (pin "6") (pinfunction "UD-_6") (pintype "passive"))
      (node (ref "USB_USART1") (pin "2") (pinfunction "D-_2") (pintype "passive"))
    )
    (net (code "13") (name "/DA1") (class "Default")
      (node (ref "DA1") (pin "1") (pinfunction "1_1") (pintype "passive"))
      (node (ref "R16") (pin "2") (pinfunction "2_2") (pintype "passive"))
      (node (ref "U3") (pin "2") (pinfunction "-IN_2") (pintype "input"))
    )
    (net (code "14") (name "/DA2") (class "Default")
      (node (ref "DA2") (pin "1") (pinfunction "1_1") (pintype "passive"))
      (node (ref "R17") (pin "2") (pinfunction "2_2") (pintype "passive"))
      (node (ref "U4") (pin "2") (pinfunction "-IN_2") (pintype "input"))
    )
    (net (code "15") (name "/DA_CLR#") (class "Default")
      (node (ref "*1") (pin "11") (pinfunction "CLR#_11") (pintype "passive"))
      (node (ref "U2") (pin "29") (pinfunction "PB10_29") (pintype "bidirectional"))
    )
    (net (code "16") (name "/DA_LDAC#") (class "Default")
      (node (ref "*1") (pin "10") (pinfunction "LDAC#_10") (pintype "passive"))
      (node (ref "U2") (pin "33") (pinfunction "PB12_33") (pintype "bidirectional"))
    )
    (net (code "17") (name "/DA_SCLK") (class "Default")
      (node (ref "*1") (pin "8") (pinfunction "SCLK_8") (pintype "passive"))
      (node (ref "U2") (pin "34") (pinfunction "PB13_34") (pintype "bidirectional"))
    )
    (net (code "18") (name "/DA_SDIN") (class "Default")
      (node (ref "*1") (pin "9") (pinfunction "SDIN_9") (pintype "passive"))
      (node (ref "U2") (pin "36") (pinfunction "PB15_36") (pintype "bidirectional"))
    )
    (net (code "19") (name "/DA_SDO") (class "Default")
      (node (ref "*1") (pin "16") (pinfunction "SDO_16") (pintype "passive"))
      (node (ref "U2") (pin "35") (pinfunction "PB14_35") (pintype "bidirectional"))
    )
    (net (code "20") (name "/DA_SYNC#") (class "Default")
      (node (ref "*1") (pin "7") (pinfunction "SYNC#_7") (pintype "passive"))
      (node (ref "U2") (pin "30") (pinfunction "PB11_30") (pintype "bidirectional"))
    )
    (net (code "21") (name "/Force+") (class "Default")
      (node (ref "Force Sensor1") (pin "2") (pinfunction "2_2") (pintype "passive"))
      (node (ref "U6") (pin "3") (pinfunction "+IN_3") (pintype "input"))
    )
    (net (code "22") (name "/Force-") (class "Default")
      (node (ref "Force Sensor1") (pin "3") (pinfunction "3_3") (pintype "passive"))
      (node (ref "U6") (pin "2") (pinfunction "-IN_2") (pintype "input"))
    )
    (net (code "23") (name "/KEY1") (class "Default")
      (node (ref "C6") (pin "1") (pinfunction "1_1") (pintype "passive"))
      (node (ref "R3") (pin "2") (pinfunction "2_2") (pintype "passive"))
      (node (ref "S1") (pin "1") (pinfunction "1_1") (pintype "passive"))
      (node (ref "U2") (pin "27") (pinfunction "PB1_27") (pintype "bidirectional"))
    )
    (net (code "24") (name "/KEY2") (class "Default")
      (node (ref "C7") (pin "1") (pinfunction "1_1") (pintype "passive"))
      (node (ref "R4") (pin "2") (pinfunction "2_2") (pintype "passive"))
      (node (ref "S2") (pin "1") (pinfunction "1_1") (pintype "passive"))
      (node (ref "U2") (pin "28") (pinfunction "PB2-BOOT1(PB2)_28") (pintype "bidirectional"))
    )
    (net (code "25") (name "/KEY3") (class "Default")
      (node (ref "C8") (pin "1") (pinfunction "1_1") (pintype "passive"))
      (node (ref "R5") (pin "2") (pinfunction "2_2") (pintype "passive"))
      (node (ref "S3") (pin "1") (pinfunction "1_1") (pintype "passive"))
      (node (ref "U2") (pin "55") (pinfunction "PB3(JTDO/TRACESWO)_55") (pintype "bidirectional"))
    )
    (net (code "26") (name "/KEY4") (class "Default")
      (node (ref "C9") (pin "1") (pinfunction "1_1") (pintype "passive"))
      (node (ref "R6") (pin "2") (pinfunction "2_2") (pintype "passive"))
      (node (ref "S4") (pin "1") (pinfunction "1_1") (pintype "passive"))
      (node (ref "U2") (pin "56") (pinfunction "PB4(NJTRST)_56") (pintype "bidirectional"))
    )
    (net (code "27") (name "/KEY5") (class "Default")
      (node (ref "C10") (pin "1") (pinfunction "1_1") (pintype "passive"))
      (node (ref "R7") (pin "2") (pinfunction "2_2") (pintype "passive"))
      (node (ref "S5") (pin "1") (pinfunction "1_1") (pintype "passive"))
      (node (ref "U2") (pin "57") (pinfunction "PB5_57") (pintype "bidirectional"))
    )
    (net (code "28") (name "/LED") (class "Default")
      (node (ref "D1") (pin "K") (pinfunction "K_K") (pintype "passive"))
      (node (ref "U2") (pin "50") (pinfunction "PA15(JTDI)_50") (pintype "bidirectional"))
    )
    (net (code "29") (name "/NRST") (class "Default")
      (node (ref "C27") (pin "1") (pinfunction "1_1") (pintype "passive"))
      (node (ref "R23") (pin "2") (pinfunction "2_2") (pintype "passive"))
      (node (ref "RESET1") (pin "1") (pinfunction "1_1") (pintype "passive"))
      (node (ref "U2") (pin "7") (pinfunction "NRST_7") (pintype "bidirectional"))
    )
    (net (code "30") (name "/OSC32_IN") (class "Default")
      (node (ref "C35") (pin "2") (pinfunction "2_2") (pintype "passive"))
      (node (ref "U2") (pin "3") (pinfunction "PC14-OSC32_IN(PC14)_3") (pintype "bidirectional"))
      (node (ref "Y2") (pin "2") (pinfunction "OSC2_2") (pintype "passive"))
    )
    (net (code "31") (name "/OSC32_OUT") (class "Default")
      (node (ref "C37") (pin "2") (pinfunction "2_2") (pintype "passive"))
      (node (ref "U2") (pin "4") (pinfunction "PC15-OSC32_OUT(PC15)_4") (pintype "bidirectional"))
      (node (ref "Y2") (pin "1") (pinfunction "OSC1_1") (pintype "passive"))
    )
    (net (code "32") (name "/OSC_IN") (class "Default")
      (node (ref "C36") (pin "2") (pinfunction "2_2") (pintype "passive"))
      (node (ref "U2") (pin "5") (pinfunction "PH0-OSC_IN(PH0)_5") (pintype "bidirectional"))
      (node (ref "Y3") (pin "3") (pinfunction "OSC2_3") (pintype "passive"))
    )
    (net (code "33") (name "/OSC_OUT") (class "Default")
      (node (ref "C38") (pin "2") (pinfunction "2_2") (pintype "passive"))
      (node (ref "U2") (pin "6") (pinfunction "PH1-OSC_OUT(PH1)_6") (pintype "bidirectional"))
      (node (ref "Y3") (pin "1") (pinfunction "OSC1_1") (pintype "passive"))
    )
    (net (code "34") (name "/POWER") (class "Default")
      (node (ref "R1") (pin "1") (pinfunction "1_1") (pintype "passive"))
      (node (ref "U2") (pin "26") (pinfunction "PB0_26") (pintype "bidirectional"))
    )
    (net (code "35") (name "/RXD") (class "Default")
      (node (ref "U2") (pin "43") (pinfunction "PA10_43") (pintype "bidirectional"))
      (node (ref "U5") (pin "2") (pinfunction "TXD_2") (pintype "passive"))
    )
    (net (code "36") (name "/RXD2") (class "Default")
      (node (ref "U1") (pin "12") (pinfunction "R1OUT_12") (pintype "output"))
      (node (ref "U2") (pin "17") (pinfunction "PA3_17") (pintype "bidirectional"))
    )
    (net (code "37") (name "/RXD2_In") (class "Default")
      (node (ref "RS②③②_Laser1") (pin "3") (pinfunction "3_3") (pintype "passive"))
      (node (ref "U1") (pin "13") (pinfunction "R1IN_13") (pintype "input"))
    )
    (net (code "38") (name "/RXD3") (class "Default")
      (node (ref "U2") (pin "52") (pinfunction "PC11_52") (pintype "bidirectional"))
      (node (ref "USART③1") (pin "3") (pinfunction "3_3") (pintype "passive"))
    )
    (net (code "39") (name "/SCL") (class "Default")
      (node (ref "*8") (pin "6") (pinfunction "SCL_6") (pintype "passive"))
      (node (ref "IIC1") (pin "3") (pinfunction "3_3") (pintype "passive"))
      (node (ref "OLED1") (pin "3") (pinfunction "3_3") (pintype "passive"))
      (node (ref "R19") (pin "1") (pinfunction "1_1") (pintype "passive"))
      (node (ref "U2") (pin "58") (pinfunction "PB6_58") (pintype "bidirectional"))
    )
    (net (code "40") (name "/SDA") (class "Default")
      (node (ref "*8") (pin "1") (pinfunction "SDA_1") (pintype "passive"))
      (node (ref "IIC1") (pin "4") (pinfunction "4_4") (pintype "passive"))
      (node (ref "OLED1") (pin "4") (pinfunction "4_4") (pintype "passive"))
      (node (ref "R22") (pin "1") (pinfunction "1_1") (pintype "passive"))
      (node (ref "U2") (pin "59") (pinfunction "PB7_59") (pintype "bidirectional"))
    )
    (net (code "41") (name "/SWCLK") (class "Default")
      (node (ref "SWD1") (pin "4") (pinfunction "4_4") (pintype "passive"))
      (node (ref "U2") (pin "49") (pinfunction "PA14(JTCK-SWCLK)_49") (pintype "bidirectional"))
    )
    (net (code "42") (name "/SWDIO") (class "Default")
      (node (ref "SWD1") (pin "2") (pinfunction "2_2") (pintype "passive"))
      (node (ref "U2") (pin "46") (pinfunction "PA13(JTMS-SWDIO)_46") (pintype "bidirectional"))
    )
    (net (code "43") (name "/TXD") (class "Default")
      (node (ref "U2") (pin "42") (pinfunction "PA9_42") (pintype "bidirectional"))
      (node (ref "U5") (pin "3") (pinfunction "RXD_3") (pintype "passive"))
    )
    (net (code "44") (name "/TXD2") (class "Default")
      (node (ref "U1") (pin "11") (pinfunction "T1IN_11") (pintype "input"))
      (node (ref "U2") (pin "16") (pinfunction "PA2_16") (pintype "bidirectional"))
    )
    (net (code "45") (name "/TXD2_Out") (class "Default")
      (node (ref "RS②③②_Laser1") (pin "2") (pinfunction "2_2") (pintype "passive"))
      (node (ref "U1") (pin "14") (pinfunction "T1OUT_14") (pintype "output"))
    )
    (net (code "46") (name "/TXD3") (class "Default")
      (node (ref "U2") (pin "51") (pinfunction "PC10_51") (pintype "bidirectional"))
      (node (ref "USART③1") (pin "2") (pinfunction "2_2") (pintype "passive"))
    )
    (net (code "47") (name "/USB_DM") (class "Default")
      (node (ref "U2") (pin "44") (pinfunction "PA11_44") (pintype "bidirectional"))
      (node (ref "USB1") (pin "2") (pinfunction "D-_2") (pintype "passive"))
    )
    (net (code "48") (name "/USB_DP") (class "Default")
      (node (ref "U2") (pin "45") (pinfunction "PA12_45") (pintype "bidirectional"))
      (node (ref "USB1") (pin "3") (pinfunction "D+_3") (pintype "passive"))
    )
    (net (code "49") (name "/VoutA") (class "Default")
      (node (ref "*1") (pin "3") (pinfunction "VoutA_3") (pintype "passive"))
      (node (ref "*5") (pin "3") (pinfunction "+IN_3") (pintype "passive"))
    )
    (net (code "50") (name "/VoutB") (class "Default")
      (node (ref "*1") (pin "23") (pinfunction "VoutB_23") (pintype "passive"))
      (node (ref "*6") (pin "3") (pinfunction "+IN_3") (pintype "passive"))
    )
    (net (code "51") (name "1.5") (class "Default")
      (node (ref "R26") (pin "2") (pinfunction "2_2") (pintype "passive"))
      (node (ref "R28") (pin "1") (pinfunction "1_1") (pintype "passive"))
      (node (ref "U3") (pin "5") (pinfunction "REF_5") (pintype "input"))
      (node (ref "U4") (pin "5") (pinfunction "REF_5") (pintype "input"))
      (node (ref "U6") (pin "5") (pinfunction "REF_5") (pintype "input"))
    )
    (net (code "52") (name "2.5V") (class "Default")
      (node (ref "*1") (pin "17") (pinfunction "REFIN_17") (pintype "passive"))
      (node (ref "*2") (pin "2") (pinfunction "V+_2") (pintype "passive"))
      (node (ref "C12") (pin "1") (pinfunction "1_1") (pintype "passive"))
      (node (ref "R9") (pin "1") (pinfunction "1_1") (pintype "passive"))
    )
    (net (code "53") (name "3.3V") (class "Default")
      (node (ref "*8") (pin "5") (pinfunction "VDD_5") (pintype "passive"))
      (node (ref "C14") (pin "2") (pinfunction "2_2") (pintype "passive"))
      (node (ref "C21") (pin "2") (pinfunction "2_2") (pintype "passive"))
      (node (ref "C22") (pin "2") (pinfunction "2_2") (pintype "passive"))
      (node (ref "C40") (pin "2") (pinfunction "2_2") (pintype "passive"))
      (node (ref "C41") (pin "2") (pinfunction "2_2") (pintype "passive"))
      (node (ref "C42") (pin "2") (pinfunction "2_2") (pintype "passive"))
      (node (ref "C43") (pin "2") (pinfunction "2_2") (pintype "passive"))
      (node (ref "C45") (pin "2") (pinfunction "2_2") (pintype "passive"))
      (node (ref "IIC1") (pin "1") (pinfunction "1_1") (pintype "passive"))
      (node (ref "L3") (pin "2") (pinfunction "2_2") (pintype "passive"))
      (node (ref "OLED1") (pin "2") (pinfunction "2_2") (pintype "passive"))
      (node (ref "R19") (pin "2") (pinfunction "2_2") (pintype "passive"))
      (node (ref "R2") (pin "1") (pinfunction "1_1") (pintype "passive"))
      (node (ref "R22") (pin "2") (pinfunction "2_2") (pintype "passive"))
      (node (ref "R23") (pin "1") (pinfunction "1_1") (pintype "passive"))
      (node (ref "R3") (pin "1") (pinfunction "1_1") (pintype "passive"))
      (node (ref "R4") (pin "1") (pinfunction "1_1") (pintype "passive"))
      (node (ref "R5") (pin "1") (pinfunction "1_1") (pintype "passive"))
      (node (ref "R6") (pin "1") (pinfunction "1_1") (pintype "passive"))
      (node (ref "R7") (pin "1") (pinfunction "1_1") (pintype "passive"))
      (node (ref "VR1") (pin "2") (pinfunction "Vout_2") (pintype "passive"))
    )
    (net (code "54") (name "5V") (class "Default")
      (node (ref "*1") (pin "14") (pinfunction "DVcc_14") (pintype "passive"))
      (node (ref "*1") (pin "5") (pinfunction "BIN/2sCOMP#_5") (pintype "passive"))
      (node (ref "C15") (pin "2") (pinfunction "2_2") (pintype "passive"))
      (node (ref "C17") (pin "1") (pinfunction "1_1") (pintype "passive"))
      (node (ref "C19") (pin "2") (pinfunction "2_2") (pintype "passive"))
      (node (ref "C2") (pin "2") (pinfunction "2_2") (pintype "passive"))
      (node (ref "C20") (pin "2") (pinfunction "2_2") (pintype "passive"))
      (node (ref "C29") (pin "2") (pinfunction "2_2") (pintype "passive"))
      (node (ref "C39") (pin "2") (pinfunction "2_2") (pintype "passive"))
      (node (ref "C5") (pin "1") (pinfunction "1_1") (pintype "passive"))
      (node (ref "Force Sensor1") (pin "4") (pinfunction "4_4") (pintype "passive"))
      (node (ref "L1") (pin "2") (pinfunction "2_2") (pintype "passive"))
      (node (ref "R12") (pin "2") (pinfunction "2_2") (pintype "passive"))
      (node (ref "R18") (pin "1") (pinfunction "1_1") (pintype "passive"))
      (node (ref "R25") (pin "2") (pinfunction "2_2") (pintype "passive"))
      (node (ref "R9") (pin "2") (pinfunction "2_2") (pintype "passive"))
      (node (ref "RS②③②_Laser1") (pin "1") (pinfunction "1_1") (pintype "passive"))
      (node (ref "SWD1") (pin "1") (pinfunction "1_1") (pintype "passive"))
      (node (ref "U1") (pin "16") (pinfunction "VCC_16") (pintype "power_in"))
      (node (ref "U5") (pin "16") (pinfunction "VCC_16") (pintype "passive"))
      (node (ref "U7") (pin "3") (pinfunction "VCC_3") (pintype "passive"))
      (node (ref "USART③1") (pin "1") (pinfunction "1_1") (pintype "passive"))
      (node (ref "USB1") (pin "1") (pinfunction "VCC_1") (pintype "passive"))
      (node (ref "USB_USART1") (pin "1") (pinfunction "VCC_1") (pintype "passive"))
      (node (ref "VR1") (pin "3") (pinfunction "Vin_3") (pintype "passive"))
    )
    (net (code "55") (name "GND") (class "Default")
      (node (ref "*1") (pin "15") (pinfunction "GND_15") (pintype "passive"))
      (node (ref "*3") (pin "1") (pinfunction "PGND_1") (pintype "passive"))
      (node (ref "*3") (pin "3") (pinfunction "AGND_3") (pintype "passive"))
      (node (ref "*4") (pin "2") (pinfunction "2_2") (pintype "passive"))
      (node (ref "*8") (pin "2") (pinfunction "VSS_2") (pintype "passive"))
      (node (ref "C10") (pin "2") (pinfunction "2_2") (pintype "passive"))
      (node (ref "C11") (pin "2") (pinfunction "2_2") (pintype "passive"))
      (node (ref "C13") (pin "1") (pinfunction "1_1") (pintype "passive"))
      (node (ref "C14") (pin "1") (pinfunction "1_1") (pintype "passive"))
      (node (ref "C15") (pin "1") (pinfunction "1_1") (pintype "passive"))
      (node (ref "C17") (pin "2") (pinfunction "2_2") (pintype "passive"))
      (node (ref "C18") (pin "2") (pinfunction "2_2") (pintype "passive"))
      (node (ref "C19") (pin "1") (pinfunction "1_1") (pintype "passive"))
      (node (ref "C2") (pin "1") (pinfunction "1_1") (pintype "passive"))
      (node (ref "C20") (pin "1") (pinfunction "1_1") (pintype "passive"))
      (node (ref "C21") (pin "1") (pinfunction "1_1") (pintype "passive"))
      (node (ref "C22") (pin "1") (pinfunction "1_1") (pintype "passive"))
      (node (ref "C27") (pin "2") (pinfunction "2_2") (pintype "passive"))
      (node (ref "C28") (pin "2") (pinfunction "2_2") (pintype "passive"))
      (node (ref "C29") (pin "1") (pinfunction "1_1") (pintype "passive"))
      (node (ref "C3") (pin "1") (pinfunction "1_1") (pintype "passive"))
      (node (ref "C30") (pin "2") (pinfunction "2_2") (pintype "passive"))
      (node (ref "C31") (pin "2") (pinfunction "2_2") (pintype "passive"))
      (node (ref "C33") (pin "1") (pinfunction "1_1") (pintype "passive"))
      (node (ref "C34") (pin "1") (pinfunction "1_1") (pintype "passive"))
      (node (ref "C35") (pin "1") (pinfunction "1_1") (pintype "passive"))
      (node (ref "C36") (pin "1") (pinfunction "1_1") (pintype "passive"))
      (node (ref "C37") (pin "1") (pinfunction "1_1") (pintype "passive"))
      (node (ref "C38") (pin "1") (pinfunction "1_1") (pintype "passive"))
      (node (ref "C39") (pin "1") (pinfunction "1_1") (pintype "passive"))
      (node (ref "C40") (pin "1") (pinfunction "1_1") (pintype "passive"))
      (node (ref "C41") (pin "1") (pinfunction "1_1") (pintype "passive"))
      (node (ref "C42") (pin "1") (pinfunction "1_1") (pintype "passive"))
      (node (ref "C43") (pin "1") (pinfunction "1_1") (pintype "passive"))
      (node (ref "C44") (pin "1") (pinfunction "1_1") (pintype "passive"))
      (node (ref "C45") (pin "1") (pinfunction "1_1") (pintype "passive"))
      (node (ref "C5") (pin "2") (pinfunction "2_2") (pintype "passive"))
      (node (ref "C6") (pin "2") (pinfunction "2_2") (pintype "passive"))
      (node (ref "C7") (pin "2") (pinfunction "2_2") (pintype "passive"))
      (node (ref "C8") (pin "2") (pinfunction "2_2") (pintype "passive"))
      (node (ref "C9") (pin "2") (pinfunction "2_2") (pintype "passive"))
      (node (ref "D2") (pin "K") (pinfunction "K_K") (pintype "passive"))
      (node (ref "IIC1") (pin "2") (pinfunction "2_2") (pintype "passive"))
      (node (ref "IN1") (pin "2") (pinfunction "2_2") (pintype "passive"))
      (node (ref "L2") (pin "1") (pinfunction "1_1") (pintype "passive"))
      (node (ref "OLED1") (pin "1") (pinfunction "1_1") (pintype "passive"))
      (node (ref "OUT1") (pin "2") (pinfunction "2_2") (pintype "passive"))
      (node (ref "R13") (pin "1") (pinfunction "1_1") (pintype "passive"))
      (node (ref "R24") (pin "2") (pinfunction "2_2") (pintype "passive"))
      (node (ref "RESET1") (pin "2") (pinfunction "2_2") (pintype "passive"))
      (node (ref "RS②③②_Laser1") (pin "4") (pinfunction "4_4") (pintype "passive"))
      (node (ref "S1") (pin "2") (pinfunction "2_2") (pintype "passive"))
      (node (ref "S2") (pin "2") (pinfunction "2_2") (pintype "passive"))
      (node (ref "S3") (pin "2") (pinfunction "2_2") (pintype "passive"))
      (node (ref "S4") (pin "2") (pinfunction "2_2") (pintype "passive"))
      (node (ref "S5") (pin "2") (pinfunction "2_2") (pintype "passive"))
      (node (ref "SWD1") (pin "3") (pinfunction "3_3") (pintype "passive"))
      (node (ref "U1") (pin "15") (pinfunction "GND_15") (pintype "power_in"))
      (node (ref "U2") (pin "12") (pinfunction "VSSA_12") (pintype "power_in"))
      (node (ref "U2") (pin "18") (pinfunction "VSS_18") (pintype "power_in"))
      (node (ref "U2") (pin "63") (pinfunction "VSS_63") (pintype "power_in"))
      (node (ref "U5") (pin "1") (pinfunction "GND_1") (pintype "passive"))
      (node (ref "U7") (pin "2") (pinfunction "GND_2") (pintype "passive"))
      (node (ref "U7") (pin "8") (pinfunction "S_8") (pintype "passive"))
      (node (ref "USART③1") (pin "4") (pinfunction "4_4") (pintype "passive"))
      (node (ref "USB1") (pin "5") (pinfunction "VSS_5") (pintype "passive"))
      (node (ref "USB_USART1") (pin "5") (pinfunction "VSS_5") (pintype "passive"))
      (node (ref "VR1") (pin "1") (pinfunction "GND_1") (pintype "passive"))
    )
    (net (code "56") (name "Net-(*3-COMP)") (class "Default")
      (node (ref "*3") (pin "5") (pinfunction "COMP_5") (pintype "passive"))
      (node (ref "R11") (pin "1") (pinfunction "1_1") (pintype "passive"))
    )
    (net (code "57") (name "Net-(*3-EN)") (class "Default")
      (node (ref "*3") (pin "6") (pinfunction "EN_6") (pintype "passive"))
      (node (ref "R10") (pin "2") (pinfunction "2_2") (pintype "passive"))
    )
    (net (code "58") (name "Net-(*3-FB)") (class "Default")
      (node (ref "*3") (pin "4") (pinfunction "FB_4") (pintype "passive"))
      (node (ref "R12") (pin "1") (pinfunction "1_1") (pintype "passive"))
      (node (ref "R13") (pin "2") (pinfunction "2_2") (pintype "passive"))
    )
    (net (code "59") (name "Net-(*3-LX-Pad7)") (class "Default")
      (node (ref "*3") (pin "7") (pinfunction "LX_7") (pintype "passive"))
      (node (ref "*3") (pin "8") (pinfunction "LX_8") (pintype "passive"))
      (node (ref "L1") (pin "1") (pinfunction "1_1") (pintype "passive"))
    )
    (net (code "60") (name "Net-(*5--IN)") (class "Default")
      (node (ref "*5") (pin "2") (pinfunction "-IN_2") (pintype "passive"))
      (node (ref "*5") (pin "6") (pinfunction "Out_6") (pintype "passive"))
      (node (ref "R16") (pin "1") (pinfunction "1_1") (pintype "passive"))
      (node (ref "U3") (pin "3") (pinfunction "+IN_3") (pintype "input"))
    )
    (net (code "61") (name "Net-(*5-Flag)") (class "Default")
      (node (ref "*5") (pin "8") (pinfunction "Flag_8") (pintype "passive"))
      (node (ref "R14") (pin "1") (pinfunction "1_1") (pintype "passive"))
    )
    (net (code "62") (name "Net-(*6--IN)") (class "Default")
      (node (ref "*6") (pin "2") (pinfunction "-IN_2") (pintype "passive"))
      (node (ref "*6") (pin "6") (pinfunction "Out_6") (pintype "passive"))
      (node (ref "R17") (pin "1") (pinfunction "1_1") (pintype "passive"))
      (node (ref "U4") (pin "3") (pinfunction "+IN_3") (pintype "input"))
    )
    (net (code "63") (name "Net-(*6-Flag)") (class "Default")
      (node (ref "*6") (pin "8") (pinfunction "Flag_8") (pintype "passive"))
      (node (ref "R15") (pin "1") (pinfunction "1_1") (pintype "passive"))
    )
    (net (code "64") (name "Net-(*7-V+)") (class "Default")
      (node (ref "*7") (pin "2") (pinfunction "V+_2") (pintype "passive"))
      (node (ref "C32") (pin "1") (pinfunction "1_1") (pintype "passive"))
      (node (ref "R25") (pin "1") (pinfunction "1_1") (pintype "passive"))
      (node (ref "R26") (pin "1") (pinfunction "1_1") (pintype "passive"))
    )
    (net (code "65") (name "Net-(C16-Pad2)") (class "Default")
      (node (ref "C16") (pin "2") (pinfunction "2_2") (pintype "passive"))
      (node (ref "R11") (pin "2") (pinfunction "2_2") (pintype "passive"))
    )
    (net (code "66") (name "Net-(D1-PadA)") (class "Default")
      (node (ref "D1") (pin "A") (pinfunction "A_A") (pintype "passive"))
      (node (ref "R2") (pin "2") (pinfunction "2_2") (pintype "passive"))
    )
    (net (code "67") (name "Net-(D2-PadA)") (class "Default")
      (node (ref "D2") (pin "A") (pinfunction "A_A") (pintype "passive"))
      (node (ref "R18") (pin "2") (pinfunction "2_2") (pintype "passive"))
    )
    (net (code "68") (name "Net-(Q1-D)") (class "Default")
      (node (ref "OUT1") (pin "1") (pinfunction "1_1") (pintype "passive"))
      (node (ref "Q1") (pin "3") (pinfunction "D_3") (pintype "passive"))
      (node (ref "R8") (pin "2") (pinfunction "2_2") (pintype "passive"))
    )
    (net (code "69") (name "Net-(Q1-G)") (class "Default")
      (node (ref "Q1") (pin "1") (pinfunction "G_1") (pintype "passive"))
      (node (ref "R1") (pin "2") (pinfunction "2_2") (pintype "passive"))
      (node (ref "R8") (pin "1") (pinfunction "1_1") (pintype "passive"))
    )
    (net (code "70") (name "Net-(R20-Pad1)") (class "Default")
      (node (ref "R20") (pin "1") (pinfunction "1_1") (pintype "passive"))
      (node (ref "U3") (pin "1") (pinfunction "RG_1") (pintype "passive"))
    )
    (net (code "71") (name "Net-(R20-Pad2)") (class "Default")
      (node (ref "R20") (pin "2") (pinfunction "2_2") (pintype "passive"))
      (node (ref "U3") (pin "8") (pinfunction "RG_8") (pintype "passive"))
    )
    (net (code "72") (name "Net-(R21-Pad1)") (class "Default")
      (node (ref "R21") (pin "1") (pinfunction "1_1") (pintype "passive"))
      (node (ref "U4") (pin "1") (pinfunction "RG_1") (pintype "passive"))
    )
    (net (code "73") (name "Net-(R21-Pad2)") (class "Default")
      (node (ref "R21") (pin "2") (pinfunction "2_2") (pintype "passive"))
      (node (ref "U4") (pin "8") (pinfunction "RG_8") (pintype "passive"))
    )
    (net (code "74") (name "Net-(R27-Pad1)") (class "Default")
      (node (ref "R27") (pin "1") (pinfunction "1_1") (pintype "passive"))
      (node (ref "U6") (pin "1") (pinfunction "RG_1") (pintype "passive"))
    )
    (net (code "75") (name "Net-(R27-Pad2)") (class "Default")
      (node (ref "R27") (pin "2") (pinfunction "2_2") (pintype "passive"))
      (node (ref "U6") (pin "8") (pinfunction "RG_8") (pintype "passive"))
    )
    (net (code "76") (name "Net-(U1-C1+)") (class "Default")
      (node (ref "C1") (pin "2") (pinfunction "2_2") (pintype "passive"))
      (node (ref "U1") (pin "1") (pinfunction "C1+_1") (pintype "passive"))
    )
    (net (code "77") (name "Net-(U1-C1-)") (class "Default")
      (node (ref "C1") (pin "1") (pinfunction "1_1") (pintype "passive"))
      (node (ref "U1") (pin "3") (pinfunction "C1-_3") (pintype "passive"))
    )
    (net (code "78") (name "Net-(U1-C2+)") (class "Default")
      (node (ref "C4") (pin "1") (pinfunction "1_1") (pintype "passive"))
      (node (ref "U1") (pin "4") (pinfunction "C2+_4") (pintype "passive"))
    )
    (net (code "79") (name "Net-(U1-C2-)") (class "Default")
      (node (ref "C4") (pin "2") (pinfunction "2_2") (pintype "passive"))
      (node (ref "U1") (pin "5") (pinfunction "C2-_5") (pintype "passive"))
    )
    (net (code "80") (name "Net-(U1-V+)") (class "Default")
      (node (ref "C3") (pin "2") (pinfunction "2_2") (pintype "passive"))
      (node (ref "U1") (pin "2") (pinfunction "V+_2") (pintype "power_in"))
    )
    (net (code "81") (name "Net-(U1-V-)") (class "Default")
      (node (ref "C11") (pin "1") (pinfunction "1_1") (pintype "passive"))
      (node (ref "U1") (pin "6") (pinfunction "V-_6") (pintype "power_in"))
    )
    (net (code "82") (name "Net-(U2A-BOOT0)") (class "Default")
      (node (ref "R24") (pin "1") (pinfunction "1_1") (pintype "passive"))
      (node (ref "U2") (pin "60") (pinfunction "BOOT0_60") (pintype "input"))
    )
    (net (code "83") (name "Net-(U2A-VCAP_1)") (class "Default")
      (node (ref "C28") (pin "1") (pinfunction "1_1") (pintype "passive"))
      (node (ref "U2") (pin "31") (pinfunction "VCAP_1_31") (pintype "power_in"))
    )
    (net (code "84") (name "Net-(U2A-VCAP_2)") (class "Default")
      (node (ref "C30") (pin "1") (pinfunction "1_1") (pintype "passive"))
      (node (ref "U2") (pin "47") (pinfunction "VCAP_2_47") (pintype "power_in"))
    )
    (net (code "85") (name "Net-(U2B-VBAT)") (class "Default")
      (node (ref "U2") (pin "1") (pinfunction "VBAT_1") (pintype "power_in"))
      (node (ref "U2") (pin "19") (pinfunction "VDD_19") (pintype "power_in"))
      (node (ref "U2") (pin "32") (pinfunction "VDD_32") (pintype "power_in"))
      (node (ref "U2") (pin "48") (pinfunction "VDD_48") (pintype "power_in"))
      (node (ref "U2") (pin "64") (pinfunction "VDD_64") (pintype "power_in"))
    )
    (net (code "86") (name "Net-(U2B-VDDA)") (class "Default")
      (node (ref "C44") (pin "2") (pinfunction "2_2") (pintype "passive"))
      (node (ref "L3") (pin "1") (pinfunction "1_1") (pintype "passive"))
      (node (ref "U2") (pin "13") (pinfunction "VDDA_13") (pintype "power_in"))
    )
    (net (code "87") (name "Net-(U5-V3.3)") (class "Default")
      (node (ref "C31") (pin "1") (pinfunction "1_1") (pintype "passive"))
      (node (ref "U5") (pin "4") (pinfunction "V3.3_4") (pintype "passive"))
    )
    (net (code "88") (name "Net-(U5-XI)") (class "Default")
      (node (ref "C33") (pin "2") (pinfunction "2_2") (pintype "passive"))
      (node (ref "U5") (pin "7") (pinfunction "XI_7") (pintype "passive"))
      (node (ref "Y1") (pin "1") (pinfunction "OSC1_1") (pintype "passive"))
    )
    (net (code "89") (name "Net-(U5-XO)") (class "Default")
      (node (ref "C34") (pin "2") (pinfunction "2_2") (pintype "passive"))
      (node (ref "U5") (pin "8") (pinfunction "XO_8") (pintype "passive"))
      (node (ref "Y1") (pin "3") (pinfunction "OSC2_3") (pintype "passive"))
    )
    (net (code "90") (name "SGND") (class "Default")
      (node (ref "*1") (pin "18") (pinfunction "DAC_GND_18") (pintype "passive"))
      (node (ref "*1") (pin "19") (pinfunction "DAC_GND_19") (pintype "passive"))
      (node (ref "*1") (pin "20") (pinfunction "SIG_GND_20") (pintype "passive"))
      (node (ref "*1") (pin "21") (pinfunction "SIG_GND_21") (pintype "passive"))
      (node (ref "*2") (pin "1") (pinfunction "V-_1") (pintype "passive"))
      (node (ref "*7") (pin "1") (pinfunction "V-_1") (pintype "passive"))
      (node (ref "C12") (pin "2") (pinfunction "2_2") (pintype "passive"))
      (node (ref "C23") (pin "2") (pinfunction "2_2") (pintype "passive"))
      (node (ref "C24") (pin "2") (pinfunction "2_2") (pintype "passive"))
      (node (ref "C25") (pin "2") (pinfunction "2_2") (pintype "passive"))
      (node (ref "C26") (pin "2") (pinfunction "2_2") (pintype "passive"))
      (node (ref "C32") (pin "2") (pinfunction "2_2") (pintype "passive"))
      (node (ref "DA1") (pin "2") (pinfunction "2_2") (pintype "passive"))
      (node (ref "DA2") (pin "2") (pinfunction "2_2") (pintype "passive"))
      (node (ref "Force Sensor1") (pin "1") (pinfunction "1_1") (pintype "passive"))
      (node (ref "L2") (pin "2") (pinfunction "2_2") (pintype "passive"))
      (node (ref "R14") (pin "2") (pinfunction "2_2") (pintype "passive"))
      (node (ref "R15") (pin "2") (pinfunction "2_2") (pintype "passive"))
      (node (ref "R28") (pin "2") (pinfunction "2_2") (pintype "passive"))
    )
    (net (code "91") (name "unconnected-(*1-NC-Pad2)") (class "Default")
      (node (ref "*1") (pin "2") (pinfunction "NC_2") (pintype "passive"))
    )
    (net (code "92") (name "unconnected-(*1-NC-Pad4)") (class "Default")
      (node (ref "*1") (pin "4") (pinfunction "NC_4") (pintype "passive"))
    )
    (net (code "93") (name "unconnected-(*1-NC-Pad6)") (class "Default")
      (node (ref "*1") (pin "6") (pinfunction "NC_6") (pintype "passive"))
    )
    (net (code "94") (name "unconnected-(*1-NC-Pad12)") (class "Default")
      (node (ref "*1") (pin "12") (pinfunction "NC_12") (pintype "passive"))
    )
    (net (code "95") (name "unconnected-(*1-NC-Pad13)") (class "Default")
      (node (ref "*1") (pin "13") (pinfunction "NC_13") (pintype "passive"))
    )
    (net (code "96") (name "unconnected-(*1-NC-Pad22)") (class "Default")
      (node (ref "*1") (pin "22") (pinfunction "NC_22") (pintype "passive"))
    )
    (net (code "97") (name "unconnected-(*2-ADJ-Pad3)") (class "Default")
      (node (ref "*2") (pin "3") (pinfunction "ADJ_3") (pintype "passive"))
    )
    (net (code "98") (name "unconnected-(*7-ADJ-Pad3)") (class "Default")
      (node (ref "*7") (pin "3") (pinfunction "ADJ_3") (pintype "passive"))
    )
    (net (code "99") (name "unconnected-(*8-NC-Pad3)") (class "Default")
      (node (ref "*8") (pin "3") (pinfunction "NC_3") (pintype "passive"))
    )
    (net (code "100") (name "unconnected-(*8-NC-Pad4)") (class "Default")
      (node (ref "*8") (pin "4") (pinfunction "NC_4") (pintype "passive"))
    )
    (net (code "101") (name "unconnected-(C16-Pad1)") (class "Default")
      (node (ref "C16") (pin "1") (pinfunction "1_1") (pintype "passive"))
    )
    (net (code "102") (name "unconnected-(IN1-Pad6)") (class "Default")
      (node (ref "IN1") (pin "6") (pinfunction "6_6") (pintype "passive"))
    )
    (net (code "103") (name "unconnected-(OUT1-Pad6)") (class "Default")
      (node (ref "OUT1") (pin "6") (pinfunction "6_6") (pintype "passive"))
    )
    (net (code "104") (name "unconnected-(T1-Pad1)") (class "Default")
      (node (ref "T1") (pin "1") (pinfunction "1_1") (pintype "passive"))
    )
    (net (code "105") (name "unconnected-(T2-Pad1)") (class "Default")
      (node (ref "T2") (pin "1") (pinfunction "1_1") (pintype "passive"))
    )
    (net (code "106") (name "unconnected-(T3-Pad1)") (class "Default")
      (node (ref "T3") (pin "1") (pinfunction "1_1") (pintype "passive"))
    )
    (net (code "107") (name "unconnected-(T4-Pad1)") (class "Default")
      (node (ref "T4") (pin "1") (pinfunction "1_1") (pintype "passive"))
    )
    (net (code "108") (name "unconnected-(U1-R2IN-Pad8)") (class "Default")
      (node (ref "U1") (pin "8") (pinfunction "R2IN_8") (pintype "input+no_connect"))
    )
    (net (code "109") (name "unconnected-(U1-R2OUT-Pad9)") (class "Default")
      (node (ref "U1") (pin "9") (pinfunction "R2OUT_9") (pintype "output"))
    )
    (net (code "110") (name "unconnected-(U1-T2IN-Pad10)") (class "Default")
      (node (ref "U1") (pin "10") (pinfunction "T2IN_10") (pintype "input+no_connect"))
    )
    (net (code "111") (name "unconnected-(U1-T2OUT-Pad7)") (class "Default")
      (node (ref "U1") (pin "7") (pinfunction "T2OUT_7") (pintype "output"))
    )
    (net (code "112") (name "unconnected-(U2A-PA0-WKUP(PA0)-Pad14)") (class "Default")
      (node (ref "U2") (pin "14") (pinfunction "PA0-WKUP(PA0)_14") (pintype "bidirectional"))
    )
    (net (code "113") (name "unconnected-(U2A-PA1-Pad15)") (class "Default")
      (node (ref "U2") (pin "15") (pinfunction "PA1_15") (pintype "bidirectional"))
    )
    (net (code "114") (name "unconnected-(U2A-PA4-Pad20)") (class "Default")
      (node (ref "U2") (pin "20") (pinfunction "PA4_20") (pintype "bidirectional"))
    )
    (net (code "115") (name "unconnected-(U2A-PA5-Pad21)") (class "Default")
      (node (ref "U2") (pin "21") (pinfunction "PA5_21") (pintype "bidirectional"))
    )
    (net (code "116") (name "unconnected-(U2A-PA6-Pad22)") (class "Default")
      (node (ref "U2") (pin "22") (pinfunction "PA6_22") (pintype "bidirectional"))
    )
    (net (code "117") (name "unconnected-(U2A-PA7-Pad23)") (class "Default")
      (node (ref "U2") (pin "23") (pinfunction "PA7_23") (pintype "bidirectional"))
    )
    (net (code "118") (name "unconnected-(U2A-PA8-Pad41)") (class "Default")
      (node (ref "U2") (pin "41") (pinfunction "PA8_41") (pintype "bidirectional"))
    )
    (net (code "119") (name "unconnected-(U2A-PC4-Pad24)") (class "Default")
      (node (ref "U2") (pin "24") (pinfunction "PC4_24") (pintype "bidirectional"))
    )
    (net (code "120") (name "unconnected-(U2A-PC5-Pad25)") (class "Default")
      (node (ref "U2") (pin "25") (pinfunction "PC5_25") (pintype "bidirectional"))
    )
    (net (code "121") (name "unconnected-(U2A-PC6-Pad37)") (class "Default")
      (node (ref "U2") (pin "37") (pinfunction "PC6_37") (pintype "bidirectional"))
    )
    (net (code "122") (name "unconnected-(U2A-PC7-Pad38)") (class "Default")
      (node (ref "U2") (pin "38") (pinfunction "PC7_38") (pintype "bidirectional"))
    )
    (net (code "123") (name "unconnected-(U2A-PC8-Pad39)") (class "Default")
      (node (ref "U2") (pin "39") (pinfunction "PC8_39") (pintype "bidirectional"))
    )
    (net (code "124") (name "unconnected-(U2A-PC9-Pad40)") (class "Default")
      (node (ref "U2") (pin "40") (pinfunction "PC9_40") (pintype "bidirectional"))
    )
    (net (code "125") (name "unconnected-(U2A-PC12-Pad53)") (class "Default")
      (node (ref "U2") (pin "53") (pinfunction "PC12_53") (pintype "bidirectional"))
    )
    (net (code "126") (name "unconnected-(U2A-PC13-Pad2)") (class "Default")
      (node (ref "U2") (pin "2") (pinfunction "PC13_2") (pintype "bidirectional"))
    )
    (net (code "127") (name "unconnected-(U2A-PD2-Pad54)") (class "Default")
      (node (ref "U2") (pin "54") (pinfunction "PD2_54") (pintype "bidirectional"))
    )
    (net (code "128") (name "unconnected-(U5-CTS#-Pad9)") (class "Default")
      (node (ref "U5") (pin "9") (pinfunction "CTS#_9") (pintype "passive"))
    )
    (net (code "129") (name "unconnected-(U5-DCD#-Pad13)") (class "Default")
      (node (ref "U5") (pin "13") (pinfunction "DCD#_13") (pintype "passive"))
    )
    (net (code "130") (name "unconnected-(U5-DSR#-Pad10)") (class "Default")
      (node (ref "U5") (pin "10") (pinfunction "DSR#_10") (pintype "passive"))
    )
    (net (code "131") (name "unconnected-(U5-DTR#-Pad12)") (class "Default")
      (node (ref "U5") (pin "12") (pinfunction "DTR#_12") (pintype "passive"))
    )
    (net (code "132") (name "unconnected-(U5-R232-Pad15)") (class "Default")
      (node (ref "U5") (pin "15") (pinfunction "R232_15") (pintype "passive"))
    )
    (net (code "133") (name "unconnected-(U5-RI#-Pad14)") (class "Default")
      (node (ref "U5") (pin "14") (pinfunction "RI#_14") (pintype "passive"))
    )
    (net (code "134") (name "unconnected-(U5-RTS#-Pad11)") (class "Default")
      (node (ref "U5") (pin "11") (pinfunction "RTS#_11") (pintype "passive"))
    )
    (net (code "135") (name "unconnected-(U7-n.c.-Pad5)") (class "Default")
      (node (ref "U7") (pin "5") (pinfunction "n.c._5") (pintype "passive"))
    )
    (net (code "136") (name "unconnected-(USB1-ID-Pad4)") (class "Default")
      (node (ref "USB1") (pin "4") (pinfunction "ID_4") (pintype "passive"))
    )
    (net (code "137") (name "unconnected-(USB_USART1-ID-Pad4)") (class "Default")
      (node (ref "USB_USART1") (pin "4") (pinfunction "ID_4") (pintype "passive"))
    )
  )
)
